# pin-led.net
KiCad netlist of a schematic drawn in EasyEDA
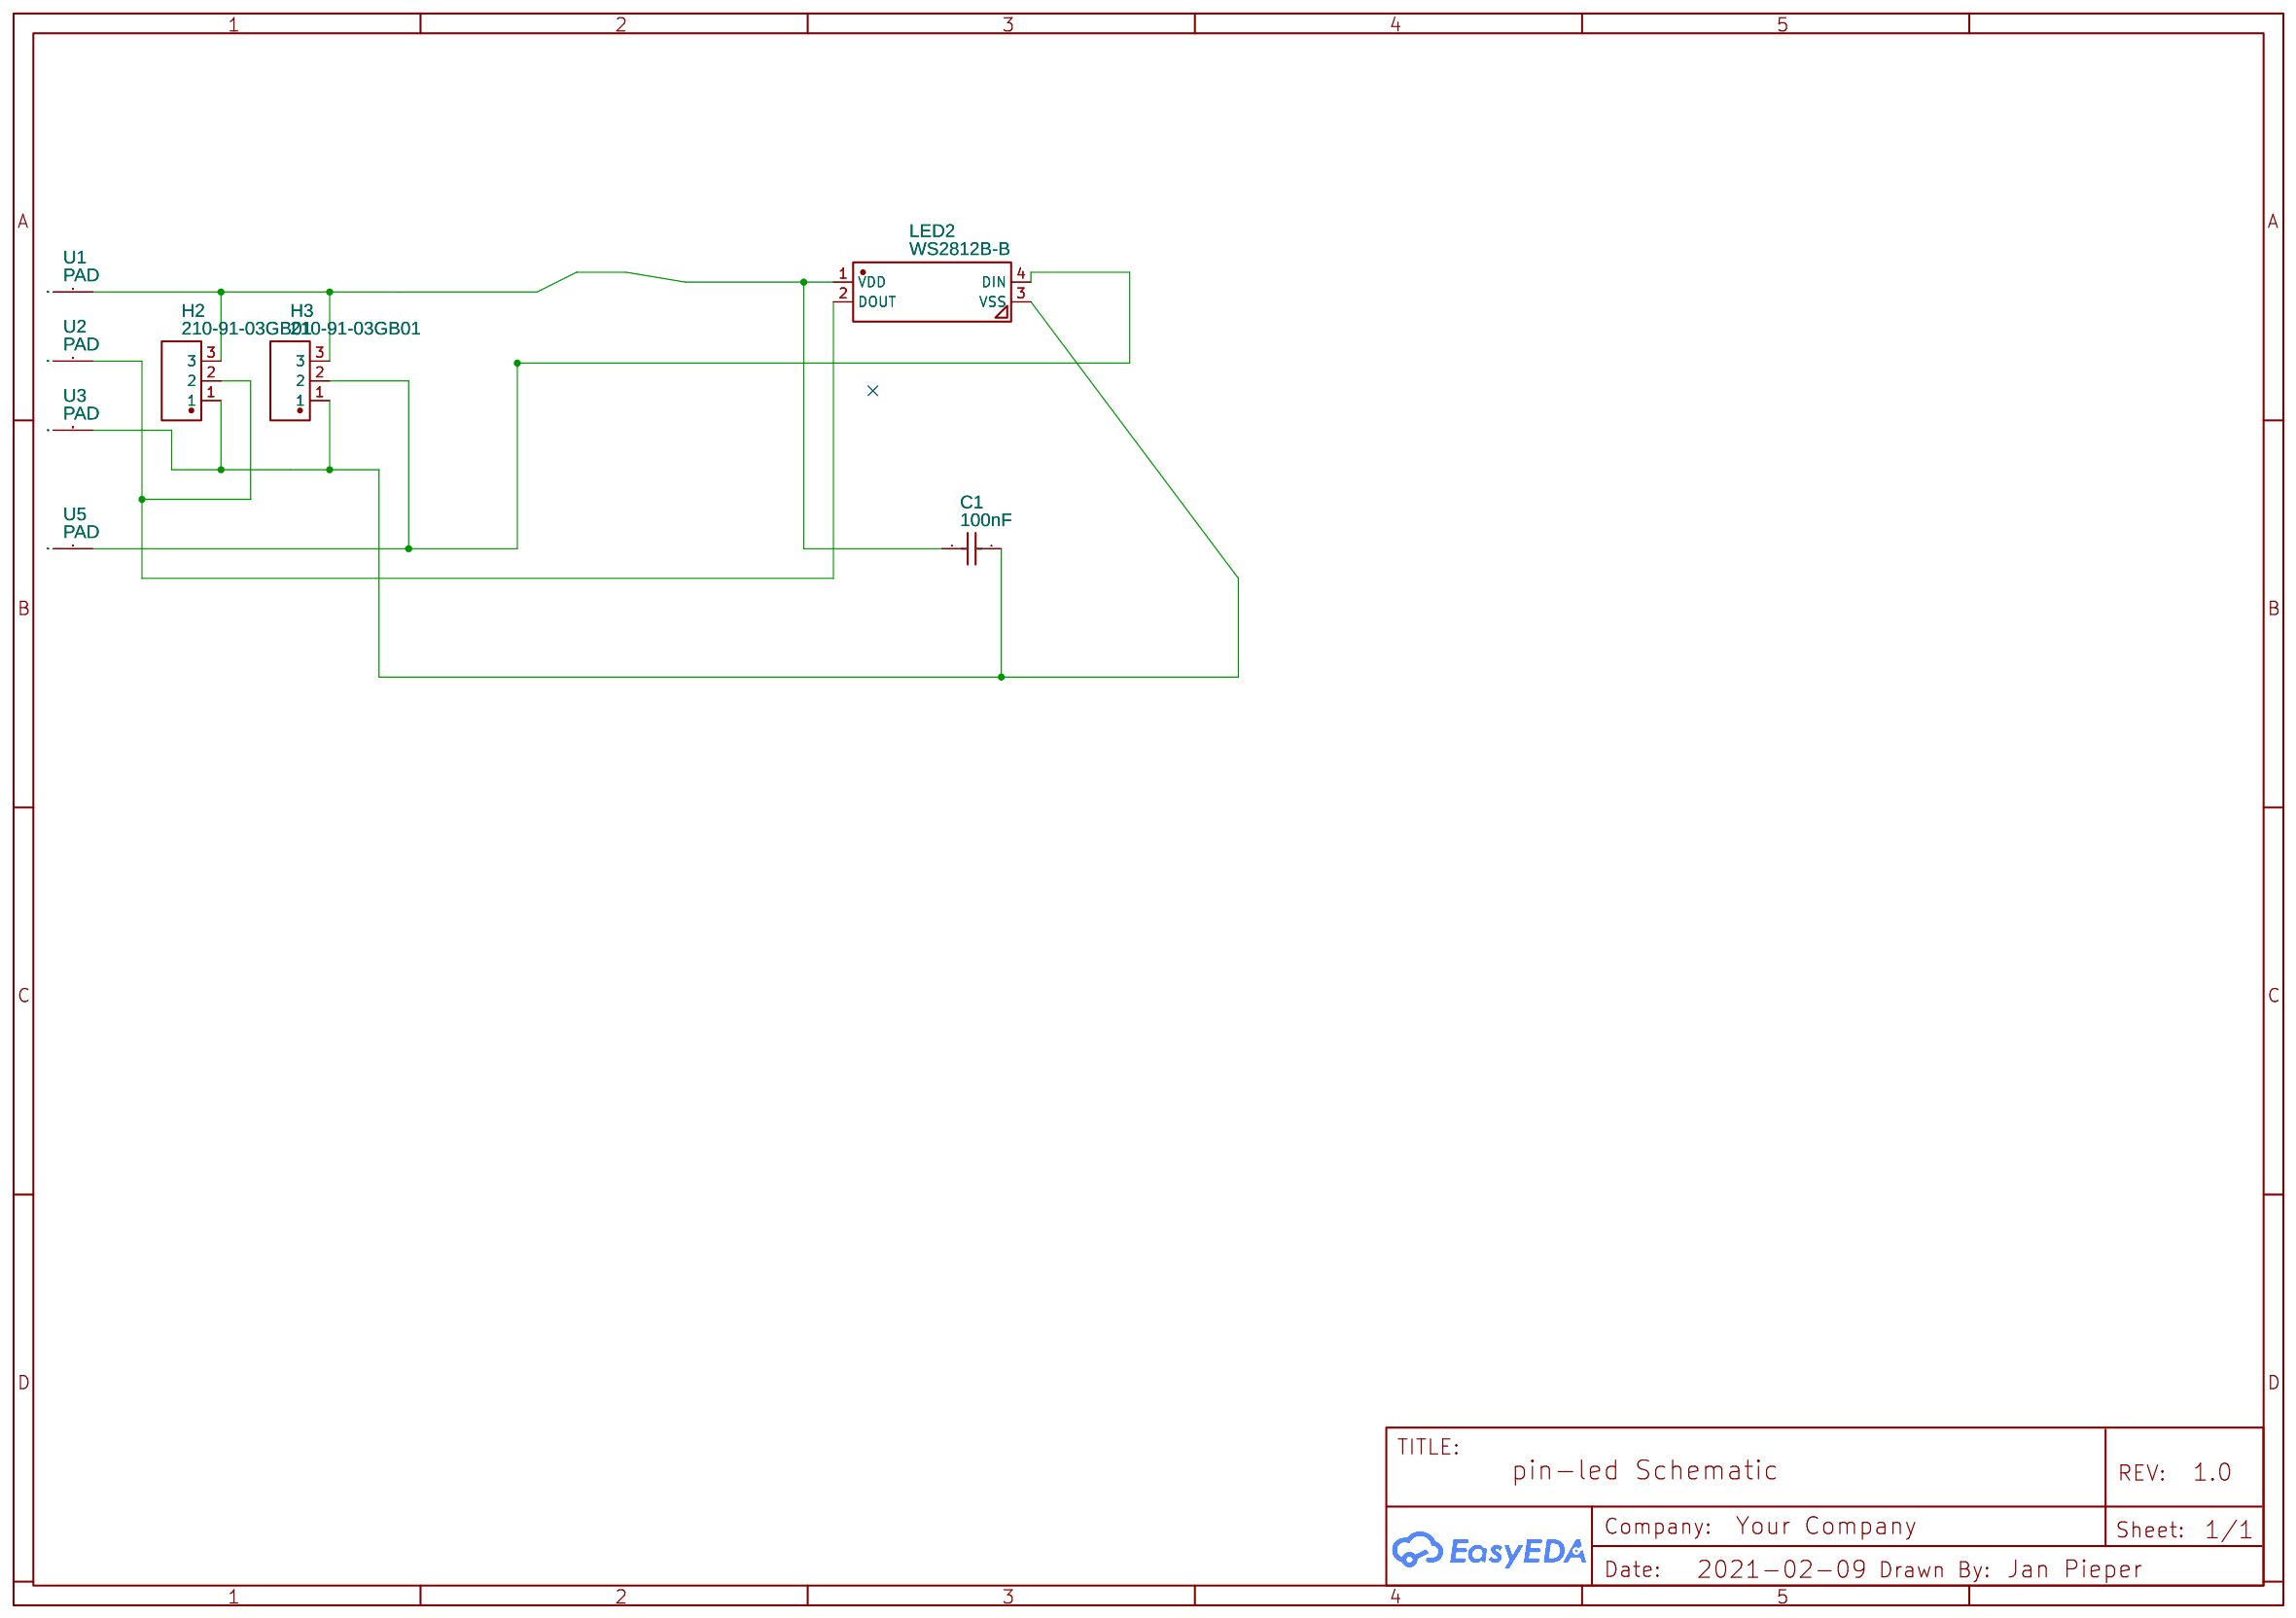
[diagram p0: schematic sheet]

(export (version "E")
  (design (tool "Eeschema 10.0.6"))
  (components
    (comp (ref "C1")
      (value "100nF")
      (fields
        (field (name "BOM_Manufacturer Part") "CL05B104KO5NNNC")
        (field (name "BOM_Supplier Part") "C1525")
      )
      (libsource (lib "") (part "CL05B104KO5NNNC"))
    )
    (comp (ref "H2")
      (value "210-91-03GB01")
      (fields (field (name "BOM_Supplier Part") "C390679"))
      (libsource (lib "") (part "210-91-03GB01"))
    )
    (comp (ref "H3")
      (value "210-91-03GB01")
      (fields (field (name "BOM_Supplier Part") "C390679"))
      (libsource (lib "") (part "210-91-03GB01"))
    )
    (comp (ref "LED2")
      (value "WS2812B-B")
      (fields (field (name "BOM_Supplier Part") "C114586"))
      (libsource (lib "") (part "WS2812B-B"))
    )
    (comp (ref "U1") (value "PAD") (libsource (lib "") (part "PAD")))
    (comp (ref "U2") (value "PAD") (libsource (lib "") (part "PAD")))
    (comp (ref "U3") (value "PAD") (libsource (lib "") (part "PAD")))
    (comp (ref "U5") (value "PAD") (libsource (lib "") (part "PAD")))
  )
  (nets
    (net (code "1") (name "Net-(LED2-DIN)") (class "Default")
      (node (ref "H3") (pin "2") (pinfunction "2_2") (pintype "unspecified"))
      (node (ref "LED2") (pin "4") (pinfunction "DIN_4") (pintype "unspecified"))
      (node (ref "U5") (pin "P$1") (pinfunction "P$1_P$1") (pintype "unspecified"))
    )
    (net (code "2") (name "Net-(LED2-DOUT)") (class "Default")
      (node (ref "H2") (pin "2") (pinfunction "2_2") (pintype "unspecified"))
      (node (ref "LED2") (pin "2") (pinfunction "DOUT_2") (pintype "unspecified"))
      (node (ref "U2") (pin "P$1") (pinfunction "P$1_P$1") (pintype "unspecified"))
    )
    (net (code "3") (name "Net-(LED2-VDD)") (class "Default")
      (node (ref "C1") (pin "1") (pinfunction "1_1") (pintype "input"))
      (node (ref "H2") (pin "3") (pinfunction "3_3") (pintype "unspecified"))
      (node (ref "H3") (pin "3") (pinfunction "3_3") (pintype "unspecified"))
      (node (ref "LED2") (pin "1") (pinfunction "VDD_1") (pintype "unspecified"))
      (node (ref "U1") (pin "P$1") (pinfunction "P$1_P$1") (pintype "unspecified"))
    )
    (net (code "4") (name "Net-(LED2-VSS)") (class "Default")
      (node (ref "C1") (pin "2") (pinfunction "2_2") (pintype "input"))
      (node (ref "H2") (pin "1") (pinfunction "1_1") (pintype "unspecified"))
      (node (ref "H3") (pin "1") (pinfunction "1_1") (pintype "unspecified"))
      (node (ref "LED2") (pin "3") (pinfunction "VSS_3") (pintype "unspecified"))
      (node (ref "U3") (pin "P$1") (pinfunction "P$1_P$1") (pintype "unspecified"))
    )
  )
)
